# SEGmeter25.net
KiCad netlist of a schematic drawn in EAGLE
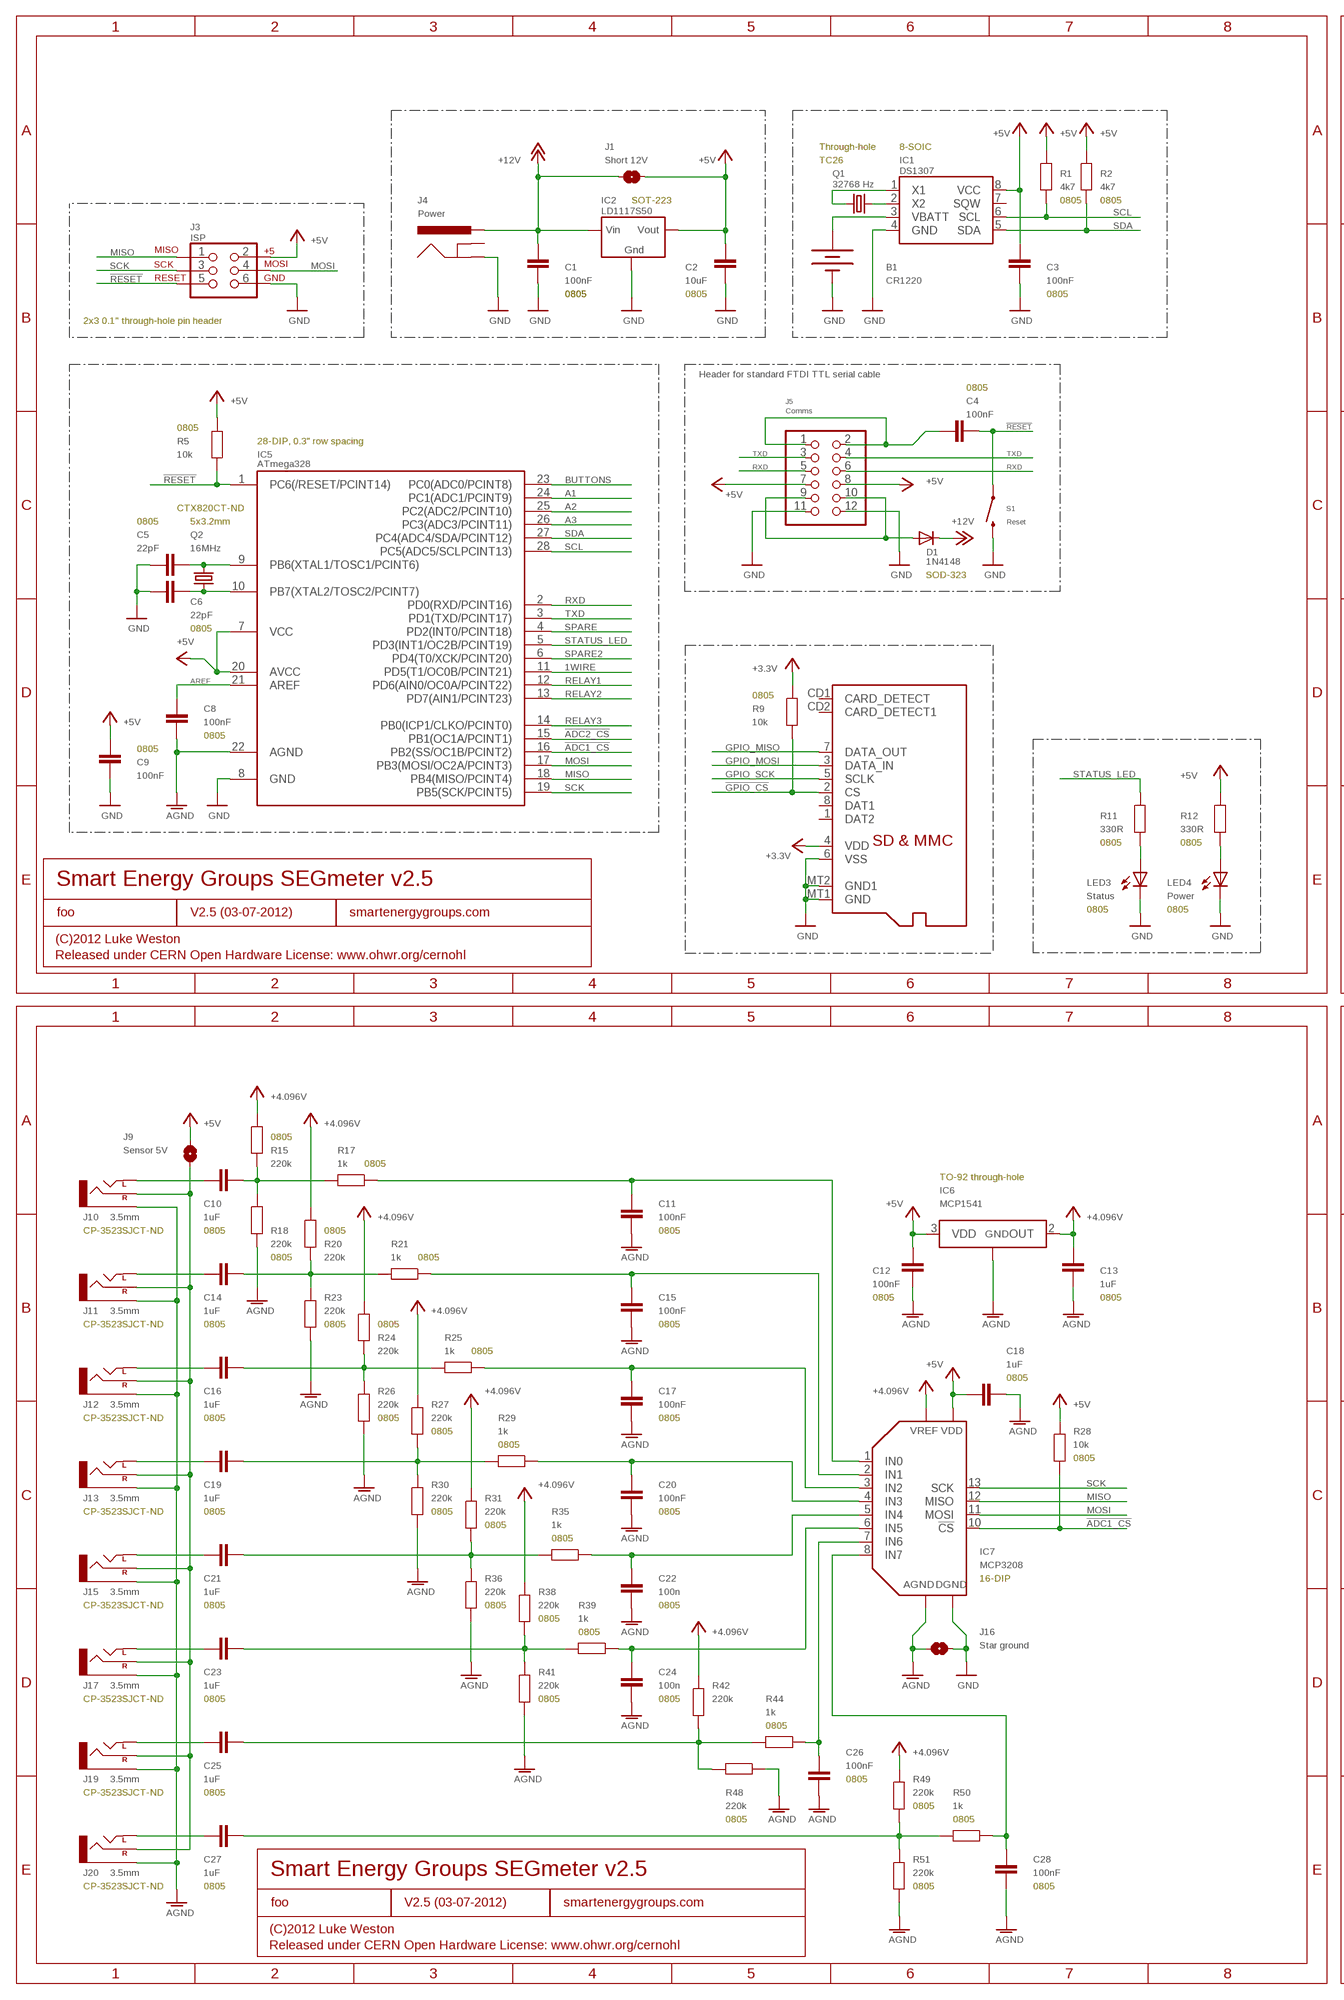
[diagram p0: schematic, sheet 1, part 1 of 2]
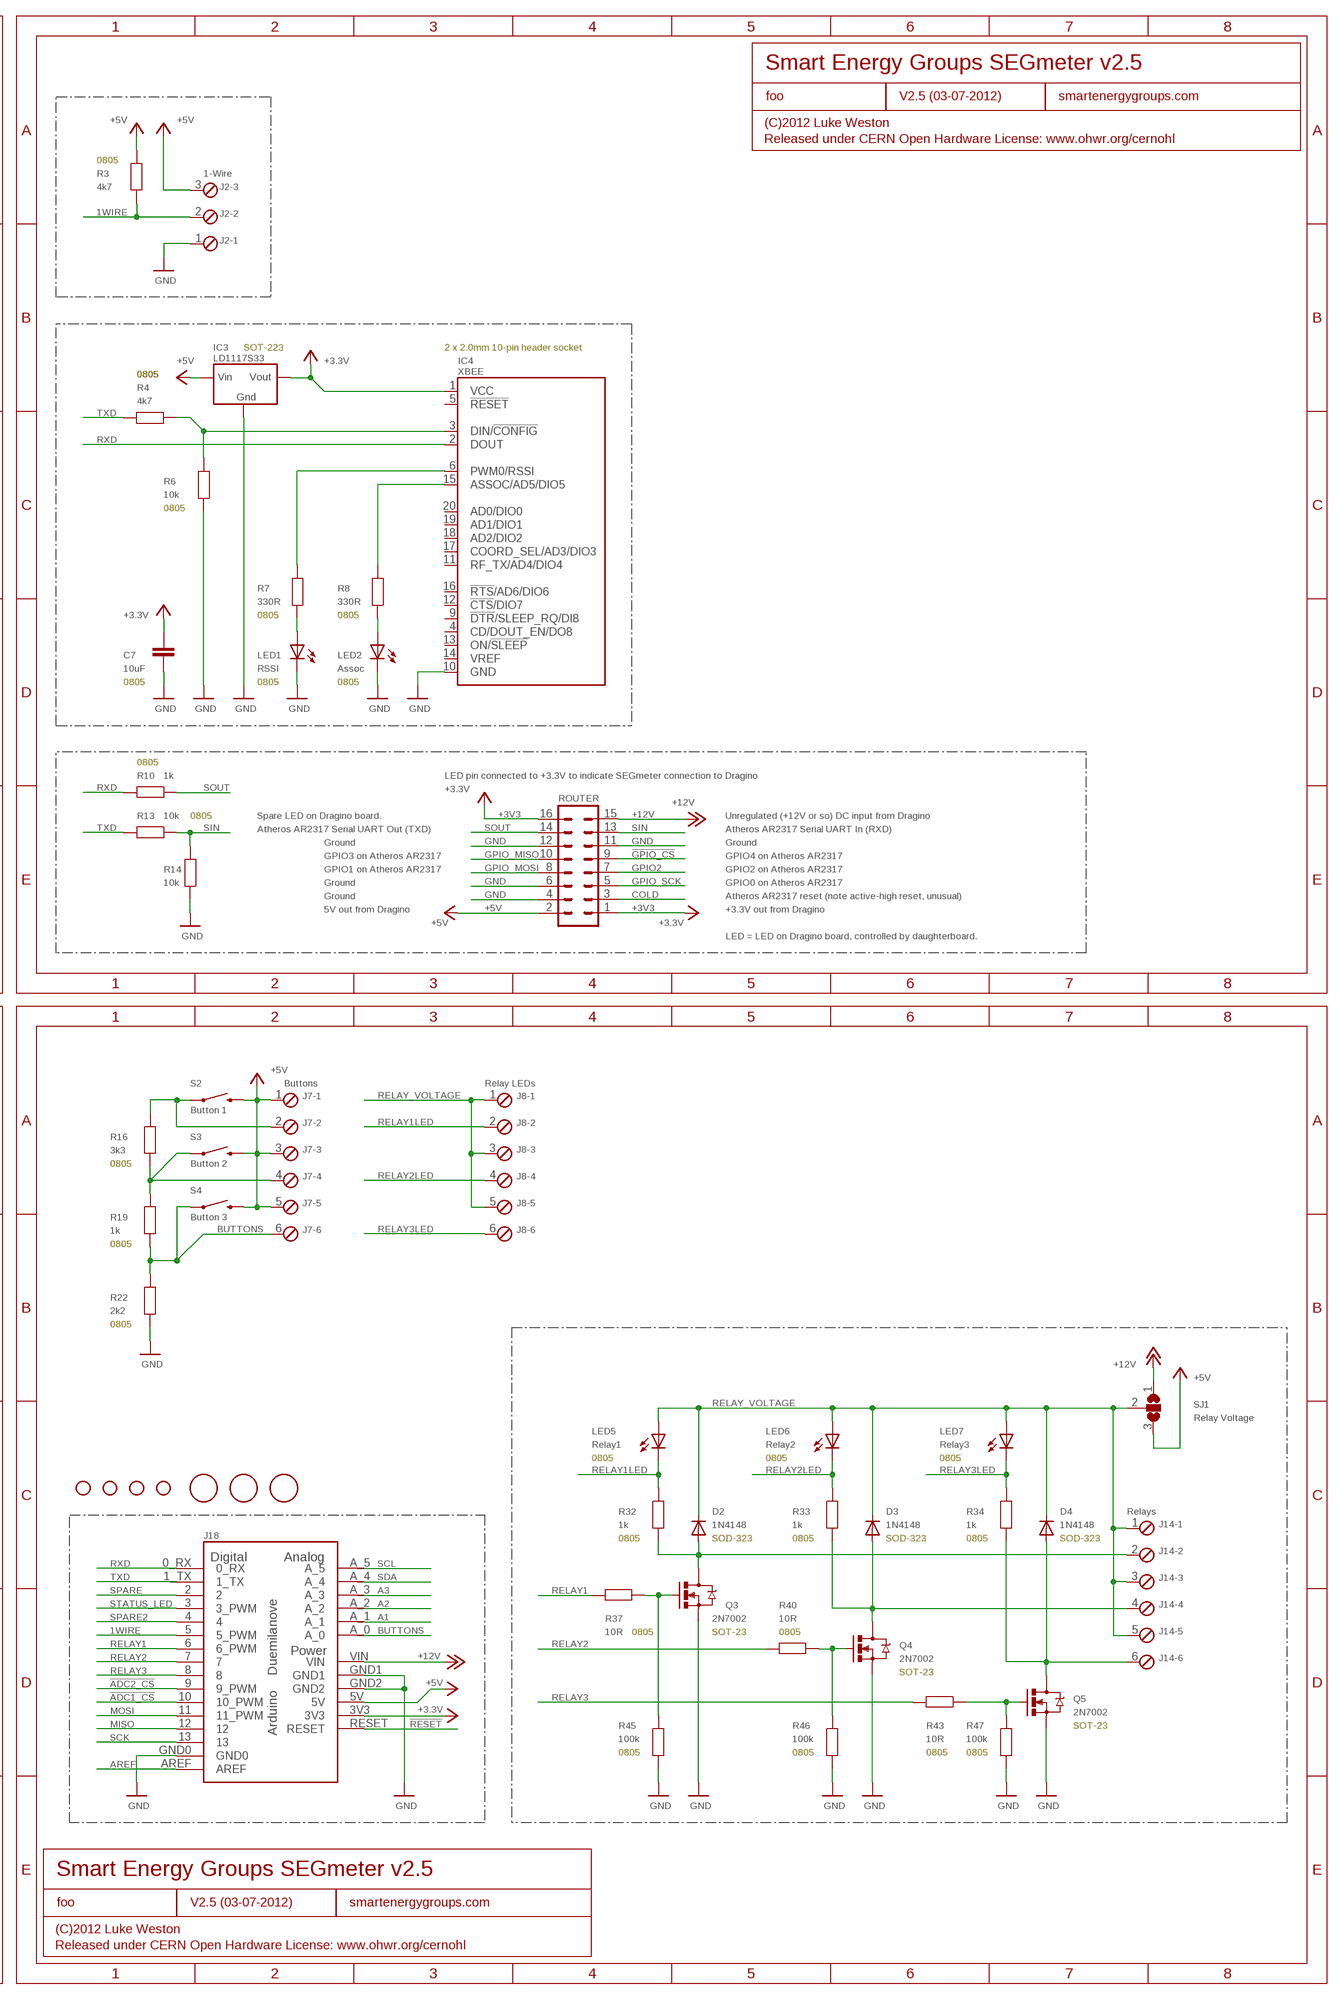
[diagram p1: schematic, sheet 1, part 2 of 2]

(export (version "E")
  (design (tool "Eeschema 10.0.6"))
  (components
    (comp (ref "B1")
      (value "CR1220")
      (footprint "eagle-import:BATTCON_12MM")
      (libsource (lib "eagle-import") (part "BATTERY12MM"))
    )
    (comp (ref "C1")
      (value "100nF")
      (footprint "eagle-import:0805")
      (libsource (lib "eagle-import") (part "CAP0805"))
    )
    (comp (ref "C2")
      (value "10uF")
      (footprint "eagle-import:0805")
      (libsource (lib "eagle-import") (part "CAP0805"))
    )
    (comp (ref "C3")
      (value "100nF")
      (footprint "eagle-import:0805")
      (libsource (lib "eagle-import") (part "CAP0805"))
    )
    (comp (ref "C4")
      (value "100nF")
      (footprint "eagle-import:0805")
      (libsource (lib "eagle-import") (part "CAP0805"))
    )
    (comp (ref "C5")
      (value "22pF")
      (footprint "eagle-import:0805")
      (libsource (lib "eagle-import") (part "CAP0805"))
    )
    (comp (ref "C6")
      (value "22pF")
      (footprint "eagle-import:0805")
      (libsource (lib "eagle-import") (part "CAP0805"))
    )
    (comp (ref "C7")
      (value "10uF")
      (footprint "eagle-import:0805")
      (libsource (lib "eagle-import") (part "CAP0805"))
    )
    (comp (ref "C8")
      (value "100nF")
      (footprint "eagle-import:0805")
      (libsource (lib "eagle-import") (part "CAP0805"))
    )
    (comp (ref "C9")
      (value "100nF")
      (footprint "eagle-import:0805")
      (libsource (lib "eagle-import") (part "CAP0805"))
    )
    (comp (ref "C10")
      (value "1uF")
      (footprint "eagle-import:0805")
      (libsource (lib "eagle-import") (part "CAP0805"))
    )
    (comp (ref "C11")
      (value "100nF")
      (footprint "eagle-import:0805")
      (libsource (lib "eagle-import") (part "CAP0805"))
    )
    (comp (ref "C12")
      (value "100nF")
      (footprint "eagle-import:0805")
      (libsource (lib "eagle-import") (part "CAP0805"))
    )
    (comp (ref "C13")
      (value "1uF")
      (footprint "eagle-import:0805")
      (libsource (lib "eagle-import") (part "CAP0805"))
    )
    (comp (ref "C14")
      (value "1uF")
      (footprint "eagle-import:0805")
      (libsource (lib "eagle-import") (part "CAP0805"))
    )
    (comp (ref "C15")
      (value "100nF")
      (footprint "eagle-import:0805")
      (libsource (lib "eagle-import") (part "CAP0805"))
    )
    (comp (ref "C16")
      (value "1uF")
      (footprint "eagle-import:0805")
      (libsource (lib "eagle-import") (part "CAP0805"))
    )
    (comp (ref "C17")
      (value "100nF")
      (footprint "eagle-import:0805")
      (libsource (lib "eagle-import") (part "CAP0805"))
    )
    (comp (ref "C18")
      (value "1uF")
      (footprint "eagle-import:0805")
      (libsource (lib "eagle-import") (part "CAP0805"))
    )
    (comp (ref "C19")
      (value "1uF")
      (footprint "eagle-import:0805")
      (libsource (lib "eagle-import") (part "CAP0805"))
    )
    (comp (ref "C20")
      (value "100nF")
      (footprint "eagle-import:0805")
      (libsource (lib "eagle-import") (part "CAP0805"))
    )
    (comp (ref "C21")
      (value "1uF")
      (footprint "eagle-import:0805")
      (libsource (lib "eagle-import") (part "CAP0805"))
    )
    (comp (ref "C22")
      (value "100n")
      (footprint "eagle-import:0805")
      (libsource (lib "eagle-import") (part "CAP0805"))
    )
    (comp (ref "C23")
      (value "1uF")
      (footprint "eagle-import:0805")
      (libsource (lib "eagle-import") (part "CAP0805"))
    )
    (comp (ref "C24")
      (value "100n")
      (footprint "eagle-import:0805")
      (libsource (lib "eagle-import") (part "CAP0805"))
    )
    (comp (ref "C25")
      (value "1uF")
      (footprint "eagle-import:0805")
      (libsource (lib "eagle-import") (part "CAP0805"))
    )
    (comp (ref "C26")
      (value "100nF")
      (footprint "eagle-import:0805")
      (libsource (lib "eagle-import") (part "CAP0805"))
    )
    (comp (ref "C27")
      (value "1uF")
      (footprint "eagle-import:0805")
      (libsource (lib "eagle-import") (part "CAP0805"))
    )
    (comp (ref "C28")
      (value "100nF")
      (footprint "eagle-import:0805")
      (libsource (lib "eagle-import") (part "CAP0805"))
    )
    (comp (ref "D1")
      (value "1N4148")
      (footprint "eagle-import:SOD-323")
      (libsource (lib "eagle-import") (part "DIODESOD"))
    )
    (comp (ref "D2")
      (value "1N4148")
      (footprint "eagle-import:SOD-323")
      (libsource (lib "eagle-import") (part "DIODESOD"))
    )
    (comp (ref "D3")
      (value "1N4148")
      (footprint "eagle-import:SOD-323")
      (libsource (lib "eagle-import") (part "DIODESOD"))
    )
    (comp (ref "D4")
      (value "1N4148")
      (footprint "eagle-import:SOD-323")
      (libsource (lib "eagle-import") (part "DIODESOD"))
    )
    (comp (ref "FID1")
      (value "FIDUCIAL")
      (footprint "eagle-import:FIDUCIAL_1MM")
      (libsource (lib "eagle-import") (part "FIDUCIAL"))
    )
    (comp (ref "FID2")
      (value "FIDUCIAL")
      (footprint "eagle-import:FIDUCIAL_1MM")
      (libsource (lib "eagle-import") (part "FIDUCIAL"))
    )
    (comp (ref "FID3")
      (value "FIDUCIAL")
      (footprint "eagle-import:FIDUCIAL_1MM")
      (libsource (lib "eagle-import") (part "FIDUCIAL"))
    )
    (comp (ref "H1")
      (value "STAND-OFF")
      (footprint "eagle-import:STAND-OFF")
      (libsource (lib "eagle-import") (part "STAND-OFF"))
    )
    (comp (ref "H2")
      (value "STAND-OFF")
      (footprint "eagle-import:STAND-OFF")
      (libsource (lib "eagle-import") (part "STAND-OFF"))
    )
    (comp (ref "H3")
      (value "STAND-OFF")
      (footprint "eagle-import:STAND-OFF")
      (libsource (lib "eagle-import") (part "STAND-OFF"))
    )
    (comp (ref "H4")
      (value "STAND-OFF")
      (footprint "eagle-import:STAND-OFF")
      (libsource (lib "eagle-import") (part "STAND-OFF"))
    )
    (comp (ref "IC1")
      (value "DS1307")
      (footprint "eagle-import:SO08")
      (libsource (lib "eagle-import") (part "DS1307SO8"))
    )
    (comp (ref "IC2")
      (value "LD1117S50")
      (footprint "eagle-import:SOT223")
      (fields (field (name "MPN") "REG1117"))
      (libsource (lib "eagle-import") (part "REG1117"))
    )
    (comp (ref "IC3")
      (value "LD1117S33")
      (footprint "eagle-import:SOT223")
      (fields (field (name "MPN") "REG1117"))
      (libsource (lib "eagle-import") (part "REG1117"))
    )
    (comp (ref "IC4")
      (value "XBEE")
      (footprint "eagle-import:XBEE-PRO")
      (libsource (lib "eagle-import") (part "XBEE"))
    )
    (comp (ref "IC5")
      (value "ATmega328")
      (footprint "eagle-import:DIL28-3")
      (libsource (lib "eagle-import") (part "MEGA48/88/168-PU"))
    )
    (comp (ref "IC6")
      (value "MCP1541")
      (footprint "eagle-import:TO92-STRAIGHT")
      (libsource (lib "eagle-import") (part "MCP1541"))
    )
    (comp (ref "IC7")
      (value "MCP3208")
      (footprint "eagle-import:DIL16")
      (libsource (lib "eagle-import") (part "MCP3208DIL"))
    )
    (comp (ref "J1")
      (value "Short 12V")
      (footprint "eagle-import:SJ")
      (libsource (lib "eagle-import") (part "SJ"))
    )
    (comp (ref "J2")
      (value "1-Wire")
      (footprint "eagle-import:3POL254")
      (libsource (lib "eagle-import") (part "MPT3"))
    )
    (comp (ref "J3")
      (value "ISP")
      (footprint "eagle-import:2X3-NS")
      (libsource (lib "eagle-import") (part "AVR_SPI_PRG_6NS"))
    )
    (comp (ref "J4")
      (value "Power")
      (footprint "eagle-import:POWER_JACK_SLOT")
      (libsource (lib "eagle-import") (part "POWER_JACKSLT"))
    )
    (comp (ref "J5")
      (value "Comms")
      (footprint "eagle-import:2X06")
      (libsource (lib "eagle-import") (part "PINHD-2X6"))
    )
    (comp (ref "J6")
      (value "MICROSD")
      (footprint "eagle-import:MICROSD")
      (libsource (lib "eagle-import") (part "MICROSD"))
    )
    (comp (ref "J7")
      (value "Buttons")
      (footprint "eagle-import:6POL254")
      (libsource (lib "eagle-import") (part "MPT6"))
    )
    (comp (ref "J8")
      (value "Relay LEDs")
      (footprint "eagle-import:6POL254")
      (libsource (lib "eagle-import") (part "MPT6"))
    )
    (comp (ref "J9")
      (value "Sensor 5V")
      (footprint "eagle-import:SJ")
      (libsource (lib "eagle-import") (part "SJ"))
    )
    (comp (ref "J10")
      (value "3.5mm")
      (footprint "eagle-import:AUDIO-JACK-3.5MM-SMD")
      (libsource (lib "eagle-import") (part "AUDIO-JACKSMD2"))
    )
    (comp (ref "J11")
      (value "3.5mm")
      (footprint "eagle-import:AUDIO-JACK-3.5MM-SMD")
      (libsource (lib "eagle-import") (part "AUDIO-JACKSMD2"))
    )
    (comp (ref "J12")
      (value "3.5mm")
      (footprint "eagle-import:AUDIO-JACK-3.5MM-SMD")
      (libsource (lib "eagle-import") (part "AUDIO-JACKSMD2"))
    )
    (comp (ref "J13")
      (value "3.5mm")
      (footprint "eagle-import:AUDIO-JACK-3.5MM-SMD")
      (libsource (lib "eagle-import") (part "AUDIO-JACKSMD2"))
    )
    (comp (ref "J14")
      (value "Relays")
      (footprint "eagle-import:6POL254")
      (libsource (lib "eagle-import") (part "MPT6"))
    )
    (comp (ref "J15")
      (value "3.5mm")
      (footprint "eagle-import:AUDIO-JACK-3.5MM-SMD")
      (libsource (lib "eagle-import") (part "AUDIO-JACKSMD2"))
    )
    (comp (ref "J16")
      (value "Star ground")
      (footprint "eagle-import:SJ")
      (libsource (lib "eagle-import") (part "SJ"))
    )
    (comp (ref "J17")
      (value "3.5mm")
      (footprint "eagle-import:AUDIO-JACK-3.5MM-SMD")
      (libsource (lib "eagle-import") (part "AUDIO-JACKSMD2"))
    )
    (comp (ref "J18")
      (value "Arduino-compatible headers")
      (footprint "eagle-import:NO-OUTLINE-OCTAGONAL-NOTEXT")
      (libsource (lib "eagle-import") (part "ARDUINO-USBNO-OUTLINE-NO-TEXT-OCTAGONAL"))
    )
    (comp (ref "J19")
      (value "3.5mm")
      (footprint "eagle-import:AUDIO-JACK-3.5MM-SMD")
      (libsource (lib "eagle-import") (part "AUDIO-JACKSMD2"))
    )
    (comp (ref "J20")
      (value "3.5mm")
      (footprint "eagle-import:AUDIO-JACK-3.5MM-SMD")
      (libsource (lib "eagle-import") (part "AUDIO-JACKSMD2"))
    )
    (comp (ref "LED1")
      (value "RSSI")
      (footprint "eagle-import:LED-0805")
      (libsource (lib "eagle-import") (part "LED0805"))
    )
    (comp (ref "LED2")
      (value "Assoc")
      (footprint "eagle-import:LED-0805")
      (libsource (lib "eagle-import") (part "LED0805"))
    )
    (comp (ref "LED3")
      (value "Status")
      (footprint "eagle-import:LED-0805")
      (libsource (lib "eagle-import") (part "LED0805"))
    )
    (comp (ref "LED4")
      (value "Power")
      (footprint "eagle-import:LED-0805")
      (libsource (lib "eagle-import") (part "LED0805"))
    )
    (comp (ref "LED5")
      (value "Relay1")
      (footprint "eagle-import:LED-0805")
      (libsource (lib "eagle-import") (part "LED0805"))
    )
    (comp (ref "LED6")
      (value "Relay2")
      (footprint "eagle-import:LED-0805")
      (libsource (lib "eagle-import") (part "LED0805"))
    )
    (comp (ref "LED7")
      (value "Relay3")
      (footprint "eagle-import:LED-0805")
      (libsource (lib "eagle-import") (part "LED0805"))
    )
    (comp (ref "Q1")
      (value "32768 Hz")
      (footprint "eagle-import:CRYSTAL-32KHZ-SMD")
      (libsource (lib "eagle-import") (part "CRYSTAL32-SMD"))
    )
    (comp (ref "Q2")
      (value "16MHz")
      (footprint "eagle-import:CRYSTAL-SMD-5X3")
      (libsource (lib "eagle-import") (part "CRYSTAL5X3"))
    )
    (comp (ref "Q3")
      (value "2N7002")
      (footprint "eagle-import:SOT23-3")
      (libsource (lib "eagle-import") (part "2N7002"))
    )
    (comp (ref "Q4")
      (value "2N7002")
      (footprint "eagle-import:SOT23-3")
      (libsource (lib "eagle-import") (part "2N7002"))
    )
    (comp (ref "Q5")
      (value "2N7002")
      (footprint "eagle-import:SOT23-3")
      (libsource (lib "eagle-import") (part "2N7002"))
    )
    (comp (ref "R1")
      (value "4k7")
      (footprint "eagle-import:0805")
      (libsource (lib "eagle-import") (part "RESISTOR0805"))
    )
    (comp (ref "R2")
      (value "4k7")
      (footprint "eagle-import:0805")
      (libsource (lib "eagle-import") (part "RESISTOR0805"))
    )
    (comp (ref "R3")
      (value "4k7")
      (footprint "eagle-import:0805")
      (libsource (lib "eagle-import") (part "RESISTOR0805"))
    )
    (comp (ref "R4")
      (value "4k7")
      (footprint "eagle-import:0805")
      (libsource (lib "eagle-import") (part "RESISTOR0805"))
    )
    (comp (ref "R5")
      (value "10k")
      (footprint "eagle-import:0805")
      (libsource (lib "eagle-import") (part "RESISTOR0805"))
    )
    (comp (ref "R6")
      (value "10k")
      (footprint "eagle-import:0805")
      (libsource (lib "eagle-import") (part "RESISTOR0805"))
    )
    (comp (ref "R7")
      (value "330R")
      (footprint "eagle-import:0805")
      (libsource (lib "eagle-import") (part "RESISTOR0805"))
    )
    (comp (ref "R8")
      (value "330R")
      (footprint "eagle-import:0805")
      (libsource (lib "eagle-import") (part "RESISTOR0805"))
    )
    (comp (ref "R9")
      (value "10k")
      (footprint "eagle-import:0805")
      (libsource (lib "eagle-import") (part "RESISTOR0805"))
    )
    (comp (ref "R10")
      (value "1k")
      (footprint "eagle-import:0805")
      (libsource (lib "eagle-import") (part "RESISTOR0805"))
    )
    (comp (ref "R11")
      (value "330R")
      (footprint "eagle-import:0805")
      (libsource (lib "eagle-import") (part "RESISTOR0805"))
    )
    (comp (ref "R12")
      (value "330R")
      (footprint "eagle-import:0805")
      (libsource (lib "eagle-import") (part "RESISTOR0805"))
    )
    (comp (ref "R13")
      (value "10k")
      (footprint "eagle-import:0805")
      (libsource (lib "eagle-import") (part "RESISTOR0805"))
    )
    (comp (ref "R14")
      (value "10k")
      (footprint "eagle-import:0805")
      (libsource (lib "eagle-import") (part "RESISTOR0805"))
    )
    (comp (ref "R15")
      (value "220k")
      (footprint "eagle-import:0805")
      (libsource (lib "eagle-import") (part "RESISTOR0805"))
    )
    (comp (ref "R16")
      (value "3k3")
      (footprint "eagle-import:0805")
      (libsource (lib "eagle-import") (part "RESISTOR0805"))
    )
    (comp (ref "R17")
      (value "1k")
      (footprint "eagle-import:0805")
      (libsource (lib "eagle-import") (part "RESISTOR0805"))
    )
    (comp (ref "R18")
      (value "220k")
      (footprint "eagle-import:0805")
      (libsource (lib "eagle-import") (part "RESISTOR0805"))
    )
    (comp (ref "R19")
      (value "1k")
      (footprint "eagle-import:0805")
      (libsource (lib "eagle-import") (part "RESISTOR0805"))
    )
    (comp (ref "R20")
      (value "220k")
      (footprint "eagle-import:0805")
      (libsource (lib "eagle-import") (part "RESISTOR0805"))
    )
    (comp (ref "R21")
      (value "1k")
      (footprint "eagle-import:0805")
      (libsource (lib "eagle-import") (part "RESISTOR0805"))
    )
    (comp (ref "R22")
      (value "2k2")
      (footprint "eagle-import:0805")
      (libsource (lib "eagle-import") (part "RESISTOR0805"))
    )
    (comp (ref "R23")
      (value "220k")
      (footprint "eagle-import:0805")
      (libsource (lib "eagle-import") (part "RESISTOR0805"))
    )
    (comp (ref "R24")
      (value "220k")
      (footprint "eagle-import:0805")
      (libsource (lib "eagle-import") (part "RESISTOR0805"))
    )
    (comp (ref "R25")
      (value "1k")
      (footprint "eagle-import:0805")
      (libsource (lib "eagle-import") (part "RESISTOR0805"))
    )
    (comp (ref "R26")
      (value "220k")
      (footprint "eagle-import:0805")
      (libsource (lib "eagle-import") (part "RESISTOR0805"))
    )
    (comp (ref "R27")
      (value "220k")
      (footprint "eagle-import:0805")
      (libsource (lib "eagle-import") (part "RESISTOR0805"))
    )
    (comp (ref "R28")
      (value "10k")
      (footprint "eagle-import:0805")
      (libsource (lib "eagle-import") (part "RESISTOR0805"))
    )
    (comp (ref "R29")
      (value "1k")
      (footprint "eagle-import:0805")
      (libsource (lib "eagle-import") (part "RESISTOR0805"))
    )
    (comp (ref "R30")
      (value "220k")
      (footprint "eagle-import:0805")
      (libsource (lib "eagle-import") (part "RESISTOR0805"))
    )
    (comp (ref "R31")
      (value "220k")
      (footprint "eagle-import:0805")
      (libsource (lib "eagle-import") (part "RESISTOR0805"))
    )
    (comp (ref "R32")
      (value "1k")
      (footprint "eagle-import:0805")
      (libsource (lib "eagle-import") (part "RESISTOR0805"))
    )
    (comp (ref "R33")
      (value "1k")
      (footprint "eagle-import:0805")
      (libsource (lib "eagle-import") (part "RESISTOR0805"))
    )
    (comp (ref "R34")
      (value "1k")
      (footprint "eagle-import:0805")
      (libsource (lib "eagle-import") (part "RESISTOR0805"))
    )
    (comp (ref "R35")
      (value "1k")
      (footprint "eagle-import:0805")
      (libsource (lib "eagle-import") (part "RESISTOR0805"))
    )
    (comp (ref "R36")
      (value "220k")
      (footprint "eagle-import:0805")
      (libsource (lib "eagle-import") (part "RESISTOR0805"))
    )
    (comp (ref "R37")
      (value "10R")
      (footprint "eagle-import:0805")
      (libsource (lib "eagle-import") (part "RESISTOR0805"))
    )
    (comp (ref "R38")
      (value "220k")
      (footprint "eagle-import:0805")
      (libsource (lib "eagle-import") (part "RESISTOR0805"))
    )
    (comp (ref "R39")
      (value "1k")
      (footprint "eagle-import:0805")
      (libsource (lib "eagle-import") (part "RESISTOR0805"))
    )
    (comp (ref "R40")
      (value "10R")
      (footprint "eagle-import:0805")
      (libsource (lib "eagle-import") (part "RESISTOR0805"))
    )
    (comp (ref "R41")
      (value "220k")
      (footprint "eagle-import:0805")
      (libsource (lib "eagle-import") (part "RESISTOR0805"))
    )
    (comp (ref "R42")
      (value "220k")
      (footprint "eagle-import:0805")
      (libsource (lib "eagle-import") (part "RESISTOR0805"))
    )
    (comp (ref "R43")
      (value "10R")
      (footprint "eagle-import:0805")
      (libsource (lib "eagle-import") (part "RESISTOR0805"))
    )
    (comp (ref "R44")
      (value "1k")
      (footprint "eagle-import:0805")
      (libsource (lib "eagle-import") (part "RESISTOR0805"))
    )
    (comp (ref "R45")
      (value "100k")
      (footprint "eagle-import:0805")
      (libsource (lib "eagle-import") (part "RESISTOR0805"))
    )
    (comp (ref "R46")
      (value "100k")
      (footprint "eagle-import:0805")
      (libsource (lib "eagle-import") (part "RESISTOR0805"))
    )
    (comp (ref "R47")
      (value "100k")
      (footprint "eagle-import:0805")
      (libsource (lib "eagle-import") (part "RESISTOR0805"))
    )
    (comp (ref "R48")
      (value "220k")
      (footprint "eagle-import:0805")
      (libsource (lib "eagle-import") (part "RESISTOR0805"))
    )
    (comp (ref "R49")
      (value "220k")
      (footprint "eagle-import:0805")
      (libsource (lib "eagle-import") (part "RESISTOR0805"))
    )
    (comp (ref "R50")
      (value "1k")
      (footprint "eagle-import:0805")
      (libsource (lib "eagle-import") (part "RESISTOR0805"))
    )
    (comp (ref "R51")
      (value "220k")
      (footprint "eagle-import:0805")
      (libsource (lib "eagle-import") (part "RESISTOR0805"))
    )
    (comp (ref "ROUTER")
      (value "MA08-2")
      (footprint "eagle-import:MA08-2")
      (libsource (lib "eagle-import") (part "MA08-2"))
    )
    (comp (ref "S1")
      (value "Reset")
      (footprint "eagle-import:TACTILE_SWITCH_SMD")
      (libsource (lib "eagle-import") (part "SWITCH-MOMENTARY-2SMD"))
    )
    (comp (ref "S2")
      (value "Button 1")
      (footprint "eagle-import:TACTILE_SWITCH_SMD")
      (libsource (lib "eagle-import") (part "SWITCH-MOMENTARY-2SMD"))
    )
    (comp (ref "S3")
      (value "Button 2")
      (footprint "eagle-import:TACTILE_SWITCH_SMD")
      (libsource (lib "eagle-import") (part "SWITCH-MOMENTARY-2SMD"))
    )
    (comp (ref "S4")
      (value "Button 3")
      (footprint "eagle-import:TACTILE_SWITCH_SMD")
      (libsource (lib "eagle-import") (part "SWITCH-MOMENTARY-2SMD"))
    )
    (comp (ref "SJ1")
      (value "Relay Voltage")
      (footprint "eagle-import:SJ_2")
      (libsource (lib "eagle-import") (part "SJ2W"))
    )
  )
  (nets
    (net (code "1") (name "+3.3V") (class "Default")
      (node (ref "C7") (pin "2") (pinfunction "2_2") (pintype "passive"))
      (node (ref "IC3") (pin "2") (pinfunction "VOUT_2") (pintype "output"))
      (node (ref "IC4") (pin "1") (pinfunction "VCC_1") (pintype "power_in"))
      (node (ref "J18") (pin "3V3") (pinfunction "3V3_3V3") (pintype "power_in"))
      (node (ref "J6") (pin "4") (pinfunction "VDD_4") (pintype "power_in"))
      (node (ref "R9") (pin "2") (pinfunction "2_2") (pintype "passive"))
      (node (ref "ROUTER") (pin "1") (pinfunction "1_1") (pintype "passive"))
      (node (ref "ROUTER") (pin "16") (pinfunction "16_16") (pintype "passive"))
    )
    (net (code "2") (name "+4.096V") (class "Default")
      (node (ref "C13") (pin "2") (pinfunction "2_2") (pintype "passive"))
      (node (ref "IC6") (pin "2") (pinfunction "OUT_2") (pintype "bidirectional"))
      (node (ref "IC7") (pin "15") (pinfunction "VREF_15") (pintype "bidirectional"))
      (node (ref "R15") (pin "2") (pinfunction "2_2") (pintype "passive"))
      (node (ref "R20") (pin "2") (pinfunction "2_2") (pintype "passive"))
      (node (ref "R24") (pin "2") (pinfunction "2_2") (pintype "passive"))
      (node (ref "R27") (pin "2") (pinfunction "2_2") (pintype "passive"))
      (node (ref "R31") (pin "2") (pinfunction "2_2") (pintype "passive"))
      (node (ref "R38") (pin "2") (pinfunction "2_2") (pintype "passive"))
      (node (ref "R42") (pin "2") (pinfunction "2_2") (pintype "passive"))
      (node (ref "R49") (pin "2") (pinfunction "2_2") (pintype "passive"))
    )
    (net (code "3") (name "+5V") (class "Default")
      (node (ref "C12") (pin "2") (pinfunction "2_2") (pintype "passive"))
      (node (ref "C18") (pin "2") (pinfunction "2_2") (pintype "passive"))
      (node (ref "C2") (pin "2") (pinfunction "2_2") (pintype "passive"))
      (node (ref "C3") (pin "2") (pinfunction "2_2") (pintype "passive"))
      (node (ref "C9") (pin "2") (pinfunction "2_2") (pintype "passive"))
      (node (ref "IC1") (pin "8") (pinfunction "VCC_8") (pintype "bidirectional"))
      (node (ref "IC2") (pin "2") (pinfunction "VOUT_2") (pintype "output"))
      (node (ref "IC3") (pin "3") (pinfunction "VIN_3") (pintype "input"))
      (node (ref "IC5") (pin "20") (pinfunction "AVCC_20") (pintype "passive"))
      (node (ref "IC5") (pin "7") (pinfunction "VCC_7") (pintype "power_in"))
      (node (ref "IC6") (pin "3") (pinfunction "VDD_3") (pintype "bidirectional"))
      (node (ref "IC7") (pin "16") (pinfunction "VDD_16") (pintype "bidirectional"))
      (node (ref "J1") (pin "2") (pinfunction "2_2") (pintype "passive"))
      (node (ref "J18") (pin "5V") (pinfunction "5V_5V") (pintype "power_in"))
      (node (ref "J2") (pin "3") (pinfunction "1_3") (pintype "passive"))
      (node (ref "J3") (pin "2") (pinfunction "2_2") (pintype "passive"))
      (node (ref "J5") (pin "7") (pinfunction "7_7") (pintype "passive"))
      (node (ref "J5") (pin "8") (pinfunction "8_8") (pintype "passive"))
      (node (ref "J7") (pin "1") (pinfunction "1_1") (pintype "passive"))
      (node (ref "J7") (pin "3") (pinfunction "1_3") (pintype "passive"))
      (node (ref "J7") (pin "5") (pinfunction "1_5") (pintype "passive"))
      (node (ref "J9") (pin "2") (pinfunction "2_2") (pintype "passive"))
      (node (ref "R1") (pin "2") (pinfunction "2_2") (pintype "passive"))
      (node (ref "R12") (pin "2") (pinfunction "2_2") (pintype "passive"))
      (node (ref "R2") (pin "2") (pinfunction "2_2") (pintype "passive"))
      (node (ref "R28") (pin "2") (pinfunction "2_2") (pintype "passive"))
      (node (ref "R3") (pin "2") (pinfunction "2_2") (pintype "passive"))
      (node (ref "R5") (pin "1") (pinfunction "1_1") (pintype "passive"))
      (node (ref "ROUTER") (pin "2") (pinfunction "2_2") (pintype "passive"))
      (node (ref "S2") (pin "3") (pinfunction "2_3") (pintype "passive"))
      (node (ref "S3") (pin "3") (pinfunction "2_3") (pintype "passive"))
      (node (ref "S4") (pin "3") (pinfunction "2_3") (pintype "passive"))
      (node (ref "SJ1") (pin "3") (pinfunction "3_3") (pintype "passive"))
    )
    (net (code "4") (name "+12V") (class "Default")
      (node (ref "C1") (pin "2") (pinfunction "2_2") (pintype "passive"))
      (node (ref "D1") (pin "1") (pinfunction "C_1") (pintype "passive"))
      (node (ref "IC2") (pin "3") (pinfunction "VIN_3") (pintype "input"))
      (node (ref "J1") (pin "1") (pinfunction "1_1") (pintype "passive"))
      (node (ref "J18") (pin "VIN") (pinfunction "VIN_VIN") (pintype "power_in"))
      (node (ref "J4") (pin "PWR") (pinfunction "PWR_PWR") (pintype "bidirectional"))
      (node (ref "ROUTER") (pin "15") (pinfunction "15_15") (pintype "passive"))
      (node (ref "SJ1") (pin "1") (pinfunction "1_1") (pintype "passive"))
    )
    (net (code "5") (name "/1WIRE") (class "Default")
      (node (ref "IC5") (pin "11") (pinfunction "PD5(T1/OC0B/PCINT21)_11") (pintype "bidirectional"))
      (node (ref "J18") (pin "5") (pinfunction "5_PWM_5") (pintype "bidirectional"))
      (node (ref "J2") (pin "2") (pinfunction "1_2") (pintype "passive"))
      (node (ref "R3") (pin "1") (pinfunction "1_1") (pintype "passive"))
    )
    (net (code "6") (name "/A1") (class "Default")
      (node (ref "IC5") (pin "24") (pinfunction "PC1(ADC1/PCINT9)_24") (pintype "bidirectional"))
      (node (ref "J18") (pin "A_1") (pinfunction "A_1_A_1") (pintype "input"))
    )
    (net (code "7") (name "/A2") (class "Default")
      (node (ref "IC5") (pin "25") (pinfunction "PC2(ADC2/PCINT10)_25") (pintype "bidirectional"))
      (node (ref "J18") (pin "A_2") (pinfunction "A_2_A_2") (pintype "input"))
    )
    (net (code "8") (name "/A3") (class "Default")
      (node (ref "IC5") (pin "26") (pinfunction "PC3(ADC3/PCINT11)_26") (pintype "bidirectional"))
      (node (ref "J18") (pin "A_3") (pinfunction "A_3_A_3") (pintype "input"))
    )
    (net (code "9") (name "/AREF") (class "Default")
      (node (ref "C8") (pin "2") (pinfunction "2_2") (pintype "passive"))
      (node (ref "IC5") (pin "21") (pinfunction "AREF_21") (pintype "passive"))
      (node (ref "J18") (pin "AREF") (pinfunction "AREF_AREF") (pintype "bidirectional"))
    )
    (net (code "10") (name "/BUTTONS") (class "Default")
      (node (ref "IC5") (pin "23") (pinfunction "PC0(ADC0/PCINT8)_23") (pintype "bidirectional"))
      (node (ref "J18") (pin "A_0") (pinfunction "A_0_A_0") (pintype "input"))
      (node (ref "J7") (pin "6") (pinfunction "1_6") (pintype "passive"))
      (node (ref "R19") (pin "1") (pinfunction "1_1") (pintype "passive"))
      (node (ref "R22") (pin "2") (pinfunction "2_2") (pintype "passive"))
      (node (ref "S4") (pin "1") (pinfunction "1_1") (pintype "passive"))
    )
    (net (code "11") (name "/COLD") (class "Default")
      (node (ref "ROUTER") (pin "3") (pinfunction "3_3") (pintype "passive"))
    )
    (net (code "12") (name "/GPIO2") (class "Default")
      (node (ref "ROUTER") (pin "7") (pinfunction "7_7") (pintype "passive"))
    )
    (net (code "13") (name "/GPIO_MISO") (class "Default")
      (node (ref "J6") (pin "7") (pinfunction "DATA_OUT_7") (pintype "output"))
      (node (ref "ROUTER") (pin "10") (pinfunction "10_10") (pintype "passive"))
    )
    (net (code "14") (name "/GPIO_MOSI") (class "Default")
      (node (ref "J6") (pin "3") (pinfunction "DATA_IN_3") (pintype "input"))
      (node (ref "ROUTER") (pin "8") (pinfunction "8_8") (pintype "passive"))
    )
    (net (code "15") (name "/GPIO_SCK") (class "Default")
      (node (ref "J6") (pin "5") (pinfunction "SCLK_5") (pintype "input"))
      (node (ref "ROUTER") (pin "5") (pinfunction "5_5") (pintype "passive"))
    )
    (net (code "16") (name "/MISO") (class "Default")
      (node (ref "IC5") (pin "18") (pinfunction "PB4(MISO/PCINT4)_18") (pintype "bidirectional"))
      (node (ref "IC7") (pin "12") (pinfunction "MISO_12") (pintype "bidirectional"))
      (node (ref "J18") (pin "12") (pinfunction "12_12") (pintype "bidirectional"))
      (node (ref "J3") (pin "1") (pinfunction "1_1") (pintype "passive"))
    )
    (net (code "17") (name "/MOSI") (class "Default")
      (node (ref "IC5") (pin "17") (pinfunction "PB3(MOSI/OC2A/PCINT3)_17") (pintype "bidirectional"))
      (node (ref "IC7") (pin "11") (pinfunction "MOSI_11") (pintype "bidirectional"))
      (node (ref "J18") (pin "11") (pinfunction "11_PWM_11") (pintype "bidirectional"))
      (node (ref "J3") (pin "4") (pinfunction "4_4") (pintype "passive"))
    )
    (net (code "18") (name "/RELAY1") (class "Default")
      (node (ref "IC5") (pin "12") (pinfunction "PD6(AIN0/OC0A/PCINT22)_12") (pintype "bidirectional"))
      (node (ref "J18") (pin "6") (pinfunction "6_PWM_6") (pintype "bidirectional"))
      (node (ref "R37") (pin "2") (pinfunction "2_2") (pintype "passive"))
    )
    (net (code "19") (name "/RELAY1LED") (class "Default")
      (node (ref "J8") (pin "2") (pinfunction "1_2") (pintype "passive"))
      (node (ref "LED5") (pin "C") (pinfunction "C_C") (pintype "passive"))
      (node (ref "R32") (pin "2") (pinfunction "2_2") (pintype "passive"))
    )
    (net (code "20") (name "/RELAY2") (class "Default")
      (node (ref "IC5") (pin "13") (pinfunction "PD7(AIN1/PCINT23)_13") (pintype "bidirectional"))
      (node (ref "J18") (pin "7") (pinfunction "7_7") (pintype "bidirectional"))
      (node (ref "R40") (pin "2") (pinfunction "2_2") (pintype "passive"))
    )
    (net (code "21") (name "/RELAY2LED") (class "Default")
      (node (ref "J8") (pin "4") (pinfunction "1_4") (pintype "passive"))
      (node (ref "LED6") (pin "C") (pinfunction "C_C") (pintype "passive"))
      (node (ref "R33") (pin "2") (pinfunction "2_2") (pintype "passive"))
    )
    (net (code "22") (name "/RELAY3") (class "Default")
      (node (ref "IC5") (pin "14") (pinfunction "PB0(ICP1/CLKO/PCINT0)_14") (pintype "bidirectional"))
      (node (ref "J18") (pin "8") (pinfunction "8_8") (pintype "bidirectional"))
      (node (ref "R43") (pin "2") (pinfunction "2_2") (pintype "passive"))
    )
    (net (code "23") (name "/RELAY3LED") (class "Default")
      (node (ref "J8") (pin "6") (pinfunction "1_6") (pintype "passive"))
      (node (ref "LED7") (pin "C") (pinfunction "C_C") (pintype "passive"))
      (node (ref "R34") (pin "2") (pinfunction "2_2") (pintype "passive"))
    )
    (net (code "24") (name "/RELAY_VOLTAGE") (class "Default")
      (node (ref "D2") (pin "1") (pinfunction "C_1") (pintype "passive"))
      (node (ref "D3") (pin "1") (pinfunction "C_1") (pintype "passive"))
      (node (ref "D4") (pin "1") (pinfunction "C_1") (pintype "passive"))
      (node (ref "J14") (pin "1") (pinfunction "1_1") (pintype "passive"))
      (node (ref "J14") (pin "3") (pinfunction "1_3") (pintype "passive"))
      (node (ref "J14") (pin "5") (pinfunction "1_5") (pintype "passive"))
      (node (ref "J8") (pin "1") (pinfunction "1_1") (pintype "passive"))
      (node (ref "J8") (pin "3") (pinfunction "1_3") (pintype "passive"))
      (node (ref "J8") (pin "5") (pinfunction "1_5") (pintype "passive"))
      (node (ref "LED5") (pin "A") (pinfunction "A_A") (pintype "passive"))
      (node (ref "LED6") (pin "A") (pinfunction "A_A") (pintype "passive"))
      (node (ref "LED7") (pin "A") (pinfunction "A_A") (pintype "passive"))
      (node (ref "SJ1") (pin "2") (pinfunction "2_2") (pintype "passive"))
    )
    (net (code "25") (name "/RXD") (class "Default")
      (node (ref "IC4") (pin "2") (pinfunction "DOUT_2") (pintype "output"))
      (node (ref "IC5") (pin "2") (pinfunction "PD0(RXD/PCINT16)_2") (pintype "bidirectional"))
      (node (ref "J18") (pin "0_RX") (pinfunction "0_RX_0_RX") (pintype "bidirectional"))
      (node (ref "J5") (pin "5") (pinfunction "5_5") (pintype "passive"))
      (node (ref "J5") (pin "6") (pinfunction "6_6") (pintype "passive"))
      (node (ref "R10") (pin "2") (pinfunction "2_2") (pintype "passive"))
    )
    (net (code "26") (name "/SCK") (class "Default")
      (node (ref "IC5") (pin "19") (pinfunction "PB5(SCK/PCINT5)_19") (pintype "bidirectional"))
      (node (ref "IC7") (pin "13") (pinfunction "SCK_13") (pintype "bidirectional"))
      (node (ref "J18") (pin "13") (pinfunction "13_13") (pintype "bidirectional"))
      (node (ref "J3") (pin "3") (pinfunction "3_3") (pintype "passive"))
    )
    (net (code "27") (name "/SCL") (class "Default")
      (node (ref "IC1") (pin "6") (pinfunction "SCL_6") (pintype "bidirectional"))
      (node (ref "IC5") (pin "28") (pinfunction "PC5(ADC5/SCLPCINT13)_28") (pintype "bidirectional"))
      (node (ref "J18") (pin "A_5") (pinfunction "A_5_A_5") (pintype "input"))
      (node (ref "R1") (pin "1") (pinfunction "1_1") (pintype "passive"))
    )
    (net (code "28") (name "/SDA") (class "Default")
      (node (ref "IC1") (pin "5") (pinfunction "SDA_5") (pintype "bidirectional"))
      (node (ref "IC5") (pin "27") (pinfunction "PC4(ADC4/SDA/PCINT12)_27") (pintype "bidirectional"))
      (node (ref "J18") (pin "A_4") (pinfunction "A_4_A_4") (pintype "input"))
      (node (ref "R2") (pin "1") (pinfunction "1_1") (pintype "passive"))
    )
    (net (code "29") (name "/SIN") (class "Default")
      (node (ref "R13") (pin "1") (pinfunction "1_1") (pintype "passive"))
      (node (ref "R14") (pin "1") (pinfunction "1_1") (pintype "passive"))
      (node (ref "ROUTER") (pin "13") (pinfunction "13_13") (pintype "passive"))
    )
    (net (code "30") (name "/SOUT") (class "Default")
      (node (ref "R10") (pin "1") (pinfunction "1_1") (pintype "passive"))
      (node (ref "ROUTER") (pin "14") (pinfunction "14_14") (pintype "passive"))
    )
    (net (code "31") (name "/SPARE") (class "Default")
      (node (ref "IC5") (pin "4") (pinfunction "PD2(INT0/PCINT18)_4") (pintype "bidirectional"))
      (node (ref "J18") (pin "2") (pinfunction "2_2") (pintype "bidirectional"))
    )
    (net (code "32") (name "/SPARE2") (class "Default")
      (node (ref "IC5") (pin "6") (pinfunction "PD4(T0/XCK/PCINT20)_6") (pintype "bidirectional"))
      (node (ref "J18") (pin "4") (pinfunction "4_4") (pintype "bidirectional"))
    )
    (net (code "33") (name "/STATUS_LED") (class "Default")
      (node (ref "IC5") (pin "5") (pinfunction "PD3(INT1/OC2B/PCINT19)_5") (pintype "bidirectional"))
      (node (ref "J18") (pin "3") (pinfunction "3_PWM_3") (pintype "bidirectional"))
      (node (ref "R11") (pin "2") (pinfunction "2_2") (pintype "passive"))
    )
    (net (code "34") (name "/TXD") (class "Default")
      (node (ref "IC5") (pin "3") (pinfunction "PD1(TXD/PCINT17)_3") (pintype "bidirectional"))
      (node (ref "J18") (pin "1_TX") (pinfunction "1_TX_1_TX") (pintype "bidirectional"))
      (node (ref "J5") (pin "3") (pinfunction "3_3") (pintype "passive"))
      (node (ref "J5") (pin "4") (pinfunction "4_4") (pintype "passive"))
      (node (ref "R13") (pin "2") (pinfunction "2_2") (pintype "passive"))
      (node (ref "R4") (pin "1") (pinfunction "1_1") (pintype "passive"))
    )
    (net (code "35") (name "/~{ADC1_CS}") (class "Default")
      (node (ref "IC5") (pin "16") (pinfunction "PB2(SS/OC1B/PCINT2)_16") (pintype "bidirectional"))
      (node (ref "IC7") (pin "10") (pinfunction "~{CS}_10") (pintype "bidirectional"))
      (node (ref "J18") (pin "10") (pinfunction "10_PWM_10") (pintype "bidirectional"))
      (node (ref "R28") (pin "1") (pinfunction "1_1") (pintype "passive"))
    )
    (net (code "36") (name "/~{ADC2_CS}") (class "Default")
      (node (ref "IC5") (pin "15") (pinfunction "PB1(OC1A/PCINT1)_15") (pintype "bidirectional"))
      (node (ref "J18") (pin "9") (pinfunction "9_PWM_9") (pintype "bidirectional"))
    )
    (net (code "37") (name "/~{GPIO_CS}") (class "Default")
      (node (ref "J6") (pin "2") (pinfunction "CS_2") (pintype "input"))
      (node (ref "R9") (pin "1") (pinfunction "1_1") (pintype "passive"))
      (node (ref "ROUTER") (pin "9") (pinfunction "9_9") (pintype "passive"))
    )
    (net (code "38") (name "/~{RESET}") (class "Default")
      (node (ref "C4") (pin "1") (pinfunction "1_1") (pintype "passive"))
      (node (ref "IC5") (pin "1") (pinfunction "PC6(/RESET/PCINT14)_1") (pintype "bidirectional"))
      (node (ref "J18") (pin "RESET") (pinfunction "RESET_RESET") (pintype "input"))
      (node (ref "J3") (pin "5") (pinfunction "5_5") (pintype "passive"))
      (node (ref "R5") (pin "2") (pinfunction "2_2") (pintype "passive"))
      (node (ref "S1") (pin "1") (pinfunction "1_1") (pintype "passive"))
    )
    (net (code "39") (name "AGND") (class "Default")
      (node (ref "C11") (pin "1") (pinfunction "1_1") (pintype "passive"))
      (node (ref "C12") (pin "1") (pinfunction "1_1") (pintype "passive"))
      (node (ref "C13") (pin "1") (pinfunction "1_1") (pintype "passive"))
      (node (ref "C15") (pin "1") (pinfunction "1_1") (pintype "passive"))
      (node (ref "C17") (pin "1") (pinfunction "1_1") (pintype "passive"))
      (node (ref "C18") (pin "1") (pinfunction "1_1") (pintype "passive"))
      (node (ref "C20") (pin "1") (pinfunction "1_1") (pintype "passive"))
      (node (ref "C22") (pin "1") (pinfunction "1_1") (pintype "passive"))
      (node (ref "C24") (pin "1") (pinfunction "1_1") (pintype "passive"))
      (node (ref "C26") (pin "1") (pinfunction "1_1") (pintype "passive"))
      (node (ref "C28") (pin "1") (pinfunction "1_1") (pintype "passive"))
      (node (ref "C8") (pin "1") (pinfunction "1_1") (pintype "passive"))
      (node (ref "IC5") (pin "22") (pinfunction "AGND_22") (pintype "power_in"))
      (node (ref "IC6") (pin "1") (pinfunction "GND_1") (pintype "bidirectional"))
      (node (ref "IC7") (pin "14") (pinfunction "AGND_14") (pintype "bidirectional"))
      (node (ref "J10") (pin "SLEEVE") (pinfunction "SLEEVE_SLEEVE") (pintype "bidirectional"))
      (node (ref "J11") (pin "SLEEVE") (pinfunction "SLEEVE_SLEEVE") (pintype "bidirectional"))
      (node (ref "J12") (pin "SLEEVE") (pinfunction "SLEEVE_SLEEVE") (pintype "bidirectional"))
      (node (ref "J13") (pin "SLEEVE") (pinfunction "SLEEVE_SLEEVE") (pintype "bidirectional"))
      (node (ref "J15") (pin "SLEEVE") (pinfunction "SLEEVE_SLEEVE") (pintype "bidirectional"))
      (node (ref "J16") (pin "2") (pinfunction "2_2") (pintype "passive"))
      (node (ref "J17") (pin "SLEEVE") (pinfunction "SLEEVE_SLEEVE") (pintype "bidirectional"))
      (node (ref "J19") (pin "SLEEVE") (pinfunction "SLEEVE_SLEEVE") (pintype "bidirectional"))
      (node (ref "J20") (pin "SLEEVE") (pinfunction "SLEEVE_SLEEVE") (pintype "bidirectional"))
      (node (ref "R18") (pin "1") (pinfunction "1_1") (pintype "passive"))
      (node (ref "R23") (pin "1") (pinfunction "1_1") (pintype "passive"))
      (node (ref "R26") (pin "1") (pinfunction "1_1") (pintype "passive"))
      (node (ref "R30") (pin "1") (pinfunction "1_1") (pintype "passive"))
      (node (ref "R36") (pin "1") (pinfunction "1_1") (pintype "passive"))
      (node (ref "R41") (pin "1") (pinfunction "1_1") (pintype "passive"))
      (node (ref "R48") (pin "1") (pinfunction "1_1") (pintype "passive"))
      (node (ref "R51") (pin "1") (pinfunction "1_1") (pintype "passive"))
    )
    (net (code "40") (name "GND") (class "Default")
      (node (ref "B1") (pin "GND") (pinfunction "-_GND") (pintype "power_in"))
      (node (ref "C1") (pin "1") (pinfunction "1_1") (pintype "passive"))
      (node (ref "C2") (pin "1") (pinfunction "1_1") (pintype "passive"))
      (node (ref "C3") (pin "1") (pinfunction "1_1") (pintype "passive"))
      (node (ref "C5") (pin "2") (pinfunction "2_2") (pintype "passive"))
      (node (ref "C6") (pin "2") (pinfunction "2_2") (pintype "passive"))
      (node (ref "C7") (pin "1") (pinfunction "1_1") (pintype "passive"))
      (node (ref "C9") (pin "1") (pinfunction "1_1") (pintype "passive"))
      (node (ref "IC1") (pin "4") (pinfunction "GND_4") (pintype "bidirectional"))
      (node (ref "IC2") (pin "1") (pinfunction "GND_1") (pintype "power_in"))
      (node (ref "IC3") (pin "1") (pinfunction "GND_1") (pintype "power_in"))
      (node (ref "IC4") (pin "10") (pinfunction "GND_10") (pintype "power_in"))
      (node (ref "IC5") (pin "8") (pinfunction "GND_8") (pintype "power_in"))
      (node (ref "IC7") (pin "9") (pinfunction "DGND_9") (pintype "bidirectional"))
      (node (ref "J16") (pin "1") (pinfunction "1_1") (pintype "passive"))
      (node (ref "J18") (pin "GND0") (pinfunction "GND0_GND0") (pintype "power_in"))
      (node (ref "J18") (pin "GND1") (pinfunction "GND1_GND1") (pintype "power_in"))
      (node (ref "J18") (pin "GND2") (pinfunction "GND2_GND2") (pintype "power_in"))
      (node (ref "J2") (pin "1") (pinfunction "1_1") (pintype "passive"))
      (node (ref "J3") (pin "6") (pinfunction "6_6") (pintype "passive"))
      (node (ref "J4") (pin "GND") (pinfunction "GND_GND") (pintype "bidirectional"))
      (node (ref "J5") (pin "11") (pinfunction "11_11") (pintype "passive"))
      (node (ref "J5") (pin "12") (pinfunction "12_12") (pintype "passive"))
      (node (ref "J6") (pin "6") (pinfunction "VSS_6") (pintype "power_in"))
      (node (ref "J6") (pin "MT1") (pinfunction "GND_MT1") (pintype "power_in"))
      (node (ref "J6") (pin "MT2") (pinfunction "GND1_MT2") (pintype "power_in"))
      (node (ref "LED1") (pin "C") (pinfunction "C_C") (pintype "passive"))
      (node (ref "LED2") (pin "C") (pinfunction "C_C") (pintype "passive"))
      (node (ref "LED3") (pin "C") (pinfunction "C_C") (pintype "passive"))
      (node (ref "LED4") (pin "C") (pinfunction "C_C") (pintype "passive"))
      (node (ref "Q3") (pin "2") (pinfunction "S_2") (pintype "passive"))
      (node (ref "Q4") (pin "2") (pinfunction "S_2") (pintype "passive"))
      (node (ref "Q5") (pin "2") (pinfunction "S_2") (pintype "passive"))
      (node (ref "R14") (pin "2") (pinfunction "2_2") (pintype "passive"))
      (node (ref "R22") (pin "1") (pinfunction "1_1") (pintype "passive"))
      (node (ref "R45") (pin "1") (pinfunction "1_1") (pintype "passive"))
      (node (ref "R46") (pin "1") (pinfunction "1_1") (pintype "passive"))
      (node (ref "R47") (pin "1") (pinfunction "1_1") (pintype "passive"))
      (node (ref "R6") (pin "2") (pinfunction "2_2") (pintype "passive"))
      (node (ref "ROUTER") (pin "11") (pinfunction "11_11") (pintype "passive"))
      (node (ref "ROUTER") (pin "12") (pinfunction "12_12") (pintype "passive"))
      (node (ref "ROUTER") (pin "4") (pinfunction "4_4") (pintype "passive"))
      (node (ref "ROUTER") (pin "6") (pinfunction "6_6") (pintype "passive"))
      (node (ref "S1") (pin "3") (pinfunction "2_3") (pintype "passive"))
    )
    (net (code "41") (name "Net-(B1-+)") (class "Default")
      (node (ref "B1") (pin "PWR@1") (pinfunction "+_PWR@1") (pintype "power_in"))
      (node (ref "IC1") (pin "3") (pinfunction "VBATT_3") (pintype "bidirectional"))
    )
    (net (code "42") (name "Net-(C4-Pad2)") (class "Default")
      (node (ref "C4") (pin "2") (pinfunction "2_2") (pintype "passive"))
      (node (ref "J5") (pin "1") (pinfunction "1_1") (pintype "passive"))
      (node (ref "J5") (pin "2") (pinfunction "2_2") (pintype "passive"))
    )
    (net (code "43") (name "Net-(C10-Pad2)") (class "Default")
      (node (ref "C10") (pin "2") (pinfunction "2_2") (pintype "passive"))
      (node (ref "R15") (pin "1") (pinfunction "1_1") (pintype "passive"))
      (node (ref "R17") (pin "2") (pinfunction "2_2") (pintype "passive"))
      (node (ref "R18") (pin "2") (pinfunction "2_2") (pintype "passive"))
    )
    (net (code "44") (name "Net-(C14-Pad2)") (class "Default")
      (node (ref "C14") (pin "2") (pinfunction "2_2") (pintype "passive"))
      (node (ref "R20") (pin "1") (pinfunction "1_1") (pintype "passive"))
      (node (ref "R21") (pin "2") (pinfunction "2_2") (pintype "passive"))
      (node (ref "R23") (pin "2") (pinfunction "2_2") (pintype "passive"))
    )
    (net (code "45") (name "Net-(C16-Pad2)") (class "Default")
      (node (ref "C16") (pin "2") (pinfunction "2_2") (pintype "passive"))
      (node (ref "R24") (pin "1") (pinfunction "1_1") (pintype "passive"))
      (node (ref "R25") (pin "2") (pinfunction "2_2") (pintype "passive"))
      (node (ref "R26") (pin "2") (pinfunction "2_2") (pintype "passive"))
    )
    (net (code "46") (name "Net-(C19-Pad2)") (class "Default")
      (node (ref "C19") (pin "2") (pinfunction "2_2") (pintype "passive"))
      (node (ref "R27") (pin "1") (pinfunction "1_1") (pintype "passive"))
      (node (ref "R29") (pin "2") (pinfunction "2_2") (pintype "passive"))
      (node (ref "R30") (pin "2") (pinfunction "2_2") (pintype "passive"))
    )
    (net (code "47") (name "Net-(C21-Pad2)") (class "Default")
      (node (ref "C21") (pin "2") (pinfunction "2_2") (pintype "passive"))
      (node (ref "R31") (pin "1") (pinfunction "1_1") (pintype "passive"))
      (node (ref "R35") (pin "2") (pinfunction "2_2") (pintype "passive"))
      (node (ref "R36") (pin "2") (pinfunction "2_2") (pintype "passive"))
    )
    (net (code "48") (name "Net-(C23-Pad2)") (class "Default")
      (node (ref "C23") (pin "2") (pinfunction "2_2") (pintype "passive"))
      (node (ref "R38") (pin "1") (pinfunction "1_1") (pintype "passive"))
      (node (ref "R39") (pin "2") (pinfunction "2_2") (pintype "passive"))
      (node (ref "R41") (pin "2") (pinfunction "2_2") (pintype "passive"))
    )
    (net (code "49") (name "Net-(C25-Pad2)") (class "Default")
      (node (ref "C25") (pin "2") (pinfunction "2_2") (pintype "passive"))
      (node (ref "R42") (pin "1") (pinfunction "1_1") (pintype "passive"))
      (node (ref "R44") (pin "2") (pinfunction "2_2") (pintype "passive"))
      (node (ref "R48") (pin "2") (pinfunction "2_2") (pintype "passive"))
    )
    (net (code "50") (name "Net-(C27-Pad2)") (class "Default")
      (node (ref "C27") (pin "2") (pinfunction "2_2") (pintype "passive"))
      (node (ref "R49") (pin "1") (pinfunction "1_1") (pintype "passive"))
      (node (ref "R50") (pin "2") (pinfunction "2_2") (pintype "passive"))
      (node (ref "R51") (pin "2") (pinfunction "2_2") (pintype "passive"))
    )
    (net (code "51") (name "Net-(D1-A)") (class "Default")
      (node (ref "D1") (pin "2") (pinfunction "A_2") (pintype "passive"))
      (node (ref "J5") (pin "10") (pinfunction "10_10") (pintype "passive"))
      (node (ref "J5") (pin "9") (pinfunction "9_9") (pintype "passive"))
    )
    (net (code "52") (name "Net-(D2-A)") (class "Default")
      (node (ref "D2") (pin "2") (pinfunction "A_2") (pintype "passive"))
      (node (ref "J14") (pin "2") (pinfunction "1_2") (pintype "passive"))
      (node (ref "Q3") (pin "3") (pinfunction "D_3") (pintype "passive"))
      (node (ref "R32") (pin "1") (pinfunction "1_1") (pintype "passive"))
    )
    (net (code "53") (name "Net-(D3-A)") (class "Default")
      (node (ref "D3") (pin "2") (pinfunction "A_2") (pintype "passive"))
      (node (ref "J14") (pin "4") (pinfunction "1_4") (pintype "passive"))
      (node (ref "Q4") (pin "3") (pinfunction "D_3") (pintype "passive"))
      (node (ref "R33") (pin "1") (pinfunction "1_1") (pintype "passive"))
    )
    (net (code "54") (name "Net-(D4-A)") (class "Default")
      (node (ref "D4") (pin "2") (pinfunction "A_2") (pintype "passive"))
      (node (ref "J14") (pin "6") (pinfunction "1_6") (pintype "passive"))
      (node (ref "Q5") (pin "3") (pinfunction "D_3") (pintype "passive"))
      (node (ref "R34") (pin "1") (pinfunction "1_1") (pintype "passive"))
    )
    (net (code "55") (name "Net-(IC1-X1)") (class "Default")
      (node (ref "IC1") (pin "1") (pinfunction "X1_1") (pintype "bidirectional"))
      (node (ref "Q1") (pin "X1") (pinfunction "1_X1") (pintype "passive"))
    )
    (net (code "56") (name "Net-(IC1-X2)") (class "Default")
      (node (ref "IC1") (pin "2") (pinfunction "X2_2") (pintype "bidirectional"))
      (node (ref "Q1") (pin "X2") (pinfunction "2_X2") (pintype "passive"))
    )
    (net (code "57") (name "Net-(IC4-ASSOC{slash}AD5{slash}DIO5)") (class "Default")
      (node (ref "IC4") (pin "15") (pinfunction "ASSOC/AD5/DIO5_15") (pintype "bidirectional"))
      (node (ref "R8") (pin "1") (pinfunction "1_1") (pintype "passive"))
    )
    (net (code "58") (name "Net-(IC4-DIN{slash}~{CONFIG})") (class "Default")
      (node (ref "IC4") (pin "3") (pinfunction "DIN/~{CONFIG}_3") (pintype "input"))
      (node (ref "R4") (pin "2") (pinfunction "2_2") (pintype "passive"))
      (node (ref "R6") (pin "1") (pinfunction "1_1") (pintype "passive"))
    )
    (net (code "59") (name "Net-(IC4-PWM0{slash}RSSI)") (class "Default")
      (node (ref "IC4") (pin "6") (pinfunction "PWM0/RSSI_6") (pintype "output"))
      (node (ref "R7") (pin "1") (pinfunction "1_1") (pintype "passive"))
    )
    (net (code "60") (name "Net-(IC5-PB6(XTAL1{slash}TOSC1{slash}PCINT6))") (class "Default")
      (node (ref "C5") (pin "1") (pinfunction "1_1") (pintype "passive"))
      (node (ref "IC5") (pin "9") (pinfunction "PB6(XTAL1/TOSC1/PCINT6)_9") (pintype "bidirectional"))
      (node (ref "Q2") (pin "1") (pinfunction "1_1") (pintype "passive"))
    )
    (net (code "61") (name "Net-(IC5-PB7(XTAL2{slash}TOSC2{slash}PCINT7))") (class "Default")
      (node (ref "C6") (pin "1") (pinfunction "1_1") (pintype "passive"))
      (node (ref "IC5") (pin "10") (pinfunction "PB7(XTAL2/TOSC2/PCINT7)_10") (pintype "bidirectional"))
      (node (ref "Q2") (pin "3") (pinfunction "2_3") (pintype "passive"))
    )
    (net (code "62") (name "Net-(IC7-IN0)") (class "Default")
      (node (ref "C11") (pin "2") (pinfunction "2_2") (pintype "passive"))
      (node (ref "IC7") (pin "1") (pinfunction "IN0_1") (pintype "bidirectional"))
      (node (ref "R17") (pin "1") (pinfunction "1_1") (pintype "passive"))
    )
    (net (code "63") (name "Net-(IC7-IN1)") (class "Default")
      (node (ref "C15") (pin "2") (pinfunction "2_2") (pintype "passive"))
      (node (ref "IC7") (pin "2") (pinfunction "IN1_2") (pintype "bidirectional"))
      (node (ref "R21") (pin "1") (pinfunction "1_1") (pintype "passive"))
    )
    (net (code "64") (name "Net-(IC7-IN2)") (class "Default")
      (node (ref "C17") (pin "2") (pinfunction "2_2") (pintype "passive"))
      (node (ref "IC7") (pin "3") (pinfunction "IN2_3") (pintype "bidirectional"))
      (node (ref "R25") (pin "1") (pinfunction "1_1") (pintype "passive"))
    )
    (net (code "65") (name "Net-(IC7-IN3)") (class "Default")
      (node (ref "C20") (pin "2") (pinfunction "2_2") (pintype "passive"))
      (node (ref "IC7") (pin "4") (pinfunction "IN3_4") (pintype "bidirectional"))
      (node (ref "R29") (pin "1") (pinfunction "1_1") (pintype "passive"))
    )
    (net (code "66") (name "Net-(IC7-IN4)") (class "Default")
      (node (ref "C22") (pin "2") (pinfunction "2_2") (pintype "passive"))
      (node (ref "IC7") (pin "5") (pinfunction "IN4_5") (pintype "bidirectional"))
      (node (ref "R35") (pin "1") (pinfunction "1_1") (pintype "passive"))
    )
    (net (code "67") (name "Net-(IC7-IN5)") (class "Default")
      (node (ref "C24") (pin "2") (pinfunction "2_2") (pintype "passive"))
      (node (ref "IC7") (pin "6") (pinfunction "IN5_6") (pintype "bidirectional"))
      (node (ref "R39") (pin "1") (pinfunction "1_1") (pintype "passive"))
    )
    (net (code "68") (name "Net-(IC7-IN6)") (class "Default")
      (node (ref "C26") (pin "2") (pinfunction "2_2") (pintype "passive"))
      (node (ref "IC7") (pin "7") (pinfunction "IN6_7") (pintype "bidirectional"))
      (node (ref "R44") (pin "1") (pinfunction "1_1") (pintype "passive"))
    )
    (net (code "69") (name "Net-(IC7-IN7)") (class "Default")
      (node (ref "C28") (pin "2") (pinfunction "2_2") (pintype "passive"))
      (node (ref "IC7") (pin "8") (pinfunction "IN7_8") (pintype "bidirectional"))
      (node (ref "R50") (pin "1") (pinfunction "1_1") (pintype "passive"))
    )
    (net (code "70") (name "Net-(J7B-1)") (class "Default")
      (node (ref "J7") (pin "2") (pinfunction "1_2") (pintype "passive"))
      (node (ref "R16") (pin "2") (pinfunction "2_2") (pintype "passive"))
      (node (ref "S2") (pin "1") (pinfunction "1_1") (pintype "passive"))
    )
    (net (code "71") (name "Net-(J7D-1)") (class "Default")
      (node (ref "J7") (pin "4") (pinfunction "1_4") (pintype "passive"))
      (node (ref "R16") (pin "1") (pinfunction "1_1") (pintype "passive"))
      (node (ref "R19") (pin "2") (pinfunction "2_2") (pintype "passive"))
      (node (ref "S3") (pin "1") (pinfunction "1_1") (pintype "passive"))
    )
    (net (code "72") (name "Net-(J10-LEFT)") (class "Default")
      (node (ref "C10") (pin "1") (pinfunction "1_1") (pintype "passive"))
      (node (ref "J10") (pin "TIP") (pinfunction "LEFT_TIP") (pintype "bidirectional"))
    )
    (net (code "73") (name "Net-(J10-RIGHT)") (class "Default")
      (node (ref "J10") (pin "RING") (pinfunction "RIGHT_RING") (pintype "bidirectional"))
      (node (ref "J11") (pin "RING") (pinfunction "RIGHT_RING") (pintype "bidirectional"))
      (node (ref "J12") (pin "RING") (pinfunction "RIGHT_RING") (pintype "bidirectional"))
      (node (ref "J13") (pin "RING") (pinfunction "RIGHT_RING") (pintype "bidirectional"))
      (node (ref "J15") (pin "RING") (pinfunction "RIGHT_RING") (pintype "bidirectional"))
      (node (ref "J17") (pin "RING") (pinfunction "RIGHT_RING") (pintype "bidirectional"))
      (node (ref "J19") (pin "RING") (pinfunction "RIGHT_RING") (pintype "bidirectional"))
      (node (ref "J20") (pin "RING") (pinfunction "RIGHT_RING") (pintype "bidirectional"))
      (node (ref "J9") (pin "1") (pinfunction "1_1") (pintype "passive"))
    )
    (net (code "74") (name "Net-(J11-LEFT)") (class "Default")
      (node (ref "C14") (pin "1") (pinfunction "1_1") (pintype "passive"))
      (node (ref "J11") (pin "TIP") (pinfunction "LEFT_TIP") (pintype "bidirectional"))
    )
    (net (code "75") (name "Net-(J12-LEFT)") (class "Default")
      (node (ref "C16") (pin "1") (pinfunction "1_1") (pintype "passive"))
      (node (ref "J12") (pin "TIP") (pinfunction "LEFT_TIP") (pintype "bidirectional"))
    )
    (net (code "76") (name "Net-(J13-LEFT)") (class "Default")
      (node (ref "C19") (pin "1") (pinfunction "1_1") (pintype "passive"))
      (node (ref "J13") (pin "TIP") (pinfunction "LEFT_TIP") (pintype "bidirectional"))
    )
    (net (code "77") (name "Net-(J15-LEFT)") (class "Default")
      (node (ref "C21") (pin "1") (pinfunction "1_1") (pintype "passive"))
      (node (ref "J15") (pin "TIP") (pinfunction "LEFT_TIP") (pintype "bidirectional"))
    )
    (net (code "78") (name "Net-(J17-LEFT)") (class "Default")
      (node (ref "C23") (pin "1") (pinfunction "1_1") (pintype "passive"))
      (node (ref "J17") (pin "TIP") (pinfunction "LEFT_TIP") (pintype "bidirectional"))
    )
    (net (code "79") (name "Net-(J19-LEFT)") (class "Default")
      (node (ref "C25") (pin "1") (pinfunction "1_1") (pintype "passive"))
      (node (ref "J19") (pin "TIP") (pinfunction "LEFT_TIP") (pintype "bidirectional"))
    )
    (net (code "80") (name "Net-(J20-LEFT)") (class "Default")
      (node (ref "C27") (pin "1") (pinfunction "1_1") (pintype "passive"))
      (node (ref "J20") (pin "TIP") (pinfunction "LEFT_TIP") (pintype "bidirectional"))
    )
    (net (code "81") (name "Net-(LED1-PadA)") (class "Default")
      (node (ref "LED1") (pin "A") (pinfunction "A_A") (pintype "passive"))
      (node (ref "R7") (pin "2") (pinfunction "2_2") (pintype "passive"))
    )
    (net (code "82") (name "Net-(LED2-PadA)") (class "Default")
      (node (ref "LED2") (pin "A") (pinfunction "A_A") (pintype "passive"))
      (node (ref "R8") (pin "2") (pinfunction "2_2") (pintype "passive"))
    )
    (net (code "83") (name "Net-(LED3-PadA)") (class "Default")
      (node (ref "LED3") (pin "A") (pinfunction "A_A") (pintype "passive"))
      (node (ref "R11") (pin "1") (pinfunction "1_1") (pintype "passive"))
    )
    (net (code "84") (name "Net-(LED4-PadA)") (class "Default")
      (node (ref "LED4") (pin "A") (pinfunction "A_A") (pintype "passive"))
      (node (ref "R12") (pin "1") (pinfunction "1_1") (pintype "passive"))
    )
    (net (code "85") (name "Net-(Q3-G)") (class "Default")
      (node (ref "Q3") (pin "1") (pinfunction "G_1") (pintype "passive"))
      (node (ref "R37") (pin "1") (pinfunction "1_1") (pintype "passive"))
      (node (ref "R45") (pin "2") (pinfunction "2_2") (pintype "passive"))
    )
    (net (code "86") (name "Net-(Q4-G)") (class "Default")
      (node (ref "Q4") (pin "1") (pinfunction "G_1") (pintype "passive"))
      (node (ref "R40") (pin "1") (pinfunction "1_1") (pintype "passive"))
      (node (ref "R46") (pin "2") (pinfunction "2_2") (pintype "passive"))
    )
    (net (code "87") (name "Net-(Q5-G)") (class "Default")
      (node (ref "Q5") (pin "1") (pinfunction "G_1") (pintype "passive"))
      (node (ref "R43") (pin "1") (pinfunction "1_1") (pintype "passive"))
      (node (ref "R47") (pin "2") (pinfunction "2_2") (pintype "passive"))
    )
    (net (code "88") (name "unconnected-(IC1-SQW-Pad7)") (class "Default")
      (node (ref "IC1") (pin "7") (pinfunction "SQW_7") (pintype "bidirectional"))
    )
    (net (code "89") (name "unconnected-(IC4-AD0{slash}DIO0-Pad20)") (class "Default")
      (node (ref "IC4") (pin "20") (pinfunction "AD0/DIO0_20") (pintype "bidirectional"))
    )
    (net (code "90") (name "unconnected-(IC4-AD1{slash}DIO1-Pad19)") (class "Default")
      (node (ref "IC4") (pin "19") (pinfunction "AD1/DIO1_19") (pintype "bidirectional"))
    )
    (net (code "91") (name "unconnected-(IC4-AD2{slash}DIO2-Pad18)") (class "Default")
      (node (ref "IC4") (pin "18") (pinfunction "AD2/DIO2_18") (pintype "bidirectional"))
    )
    (net (code "92") (name "unconnected-(IC4-CD{slash}DOUT_EN{slash}DO8-Pad4)") (class "Default")
      (node (ref "IC4") (pin "4") (pinfunction "CD/DOUT_EN/DO8_4") (pintype "output"))
    )
    (net (code "93") (name "unconnected-(IC4-COORD_SEL{slash}AD3{slash}DIO3-Pad17)") (class "Default")
      (node (ref "IC4") (pin "17") (pinfunction "COORD_SEL/AD3/DIO3_17") (pintype "bidirectional"))
    )
    (net (code "94") (name "unconnected-(IC4-ON{slash}~{SLEEP}-Pad13)") (class "Default")
      (node (ref "IC4") (pin "13") (pinfunction "ON/~{SLEEP}_13") (pintype "output"))
    )
    (net (code "95") (name "unconnected-(IC4-RF_TX{slash}AD4{slash}DIO4-Pad11)") (class "Default")
      (node (ref "IC4") (pin "11") (pinfunction "RF_TX/AD4/DIO4_11") (pintype "bidirectional"))
    )
    (net (code "96") (name "unconnected-(IC4-VREF-Pad14)") (class "Default")
      (node (ref "IC4") (pin "14") (pinfunction "VREF_14") (pintype "input"))
    )
    (net (code "97") (name "unconnected-(IC4-~{CTS}{slash}DIO7-Pad12)") (class "Default")
      (node (ref "IC4") (pin "12") (pinfunction "~{CTS}/DIO7_12") (pintype "bidirectional"))
    )
    (net (code "98") (name "unconnected-(IC4-~{DTR}{slash}SLEEP_RQ{slash}DI8-Pad9)") (class "Default")
      (node (ref "IC4") (pin "9") (pinfunction "~{DTR}/SLEEP_RQ/DI8_9") (pintype "bidirectional"))
    )
    (net (code "99") (name "unconnected-(IC4-~{RESET}-Pad5)") (class "Default")
      (node (ref "IC4") (pin "5") (pinfunction "~{RESET}_5") (pintype "input"))
    )
    (net (code "100") (name "unconnected-(IC4-~{RTS}{slash}AD6{slash}DIO6-Pad16)") (class "Default")
      (node (ref "IC4") (pin "16") (pinfunction "~{RTS}/AD6/DIO6_16") (pintype "bidirectional"))
    )
    (net (code "101") (name "unconnected-(J4-GNDBREAK-PadSW)") (class "Default")
      (node (ref "J4") (pin "SW") (pinfunction "GNDBREAK_SW") (pintype "bidirectional"))
    )
    (net (code "102") (name "unconnected-(J6-CARD_DETECT-PadCD1)") (class "Default")
      (node (ref "J6") (pin "CD1") (pinfunction "CARD_DETECT_CD1") (pintype "passive"))
    )
    (net (code "103") (name "unconnected-(J6-CARD_DETECT1-PadCD2)") (class "Default")
      (node (ref "J6") (pin "CD2") (pinfunction "CARD_DETECT1_CD2") (pintype "passive"))
    )
    (net (code "104") (name "unconnected-(J6-DAT1-Pad8)") (class "Default")
      (node (ref "J6") (pin "8") (pinfunction "DAT1_8") (pintype "bidirectional"))
    )
    (net (code "105") (name "unconnected-(J6-DAT2-Pad1)") (class "Default")
      (node (ref "J6") (pin "1") (pinfunction "DAT2_1") (pintype "bidirectional"))
    )
  )
)
